# lamps_antenna.net
KiCad netlist of a schematic drawn in Altium Designer
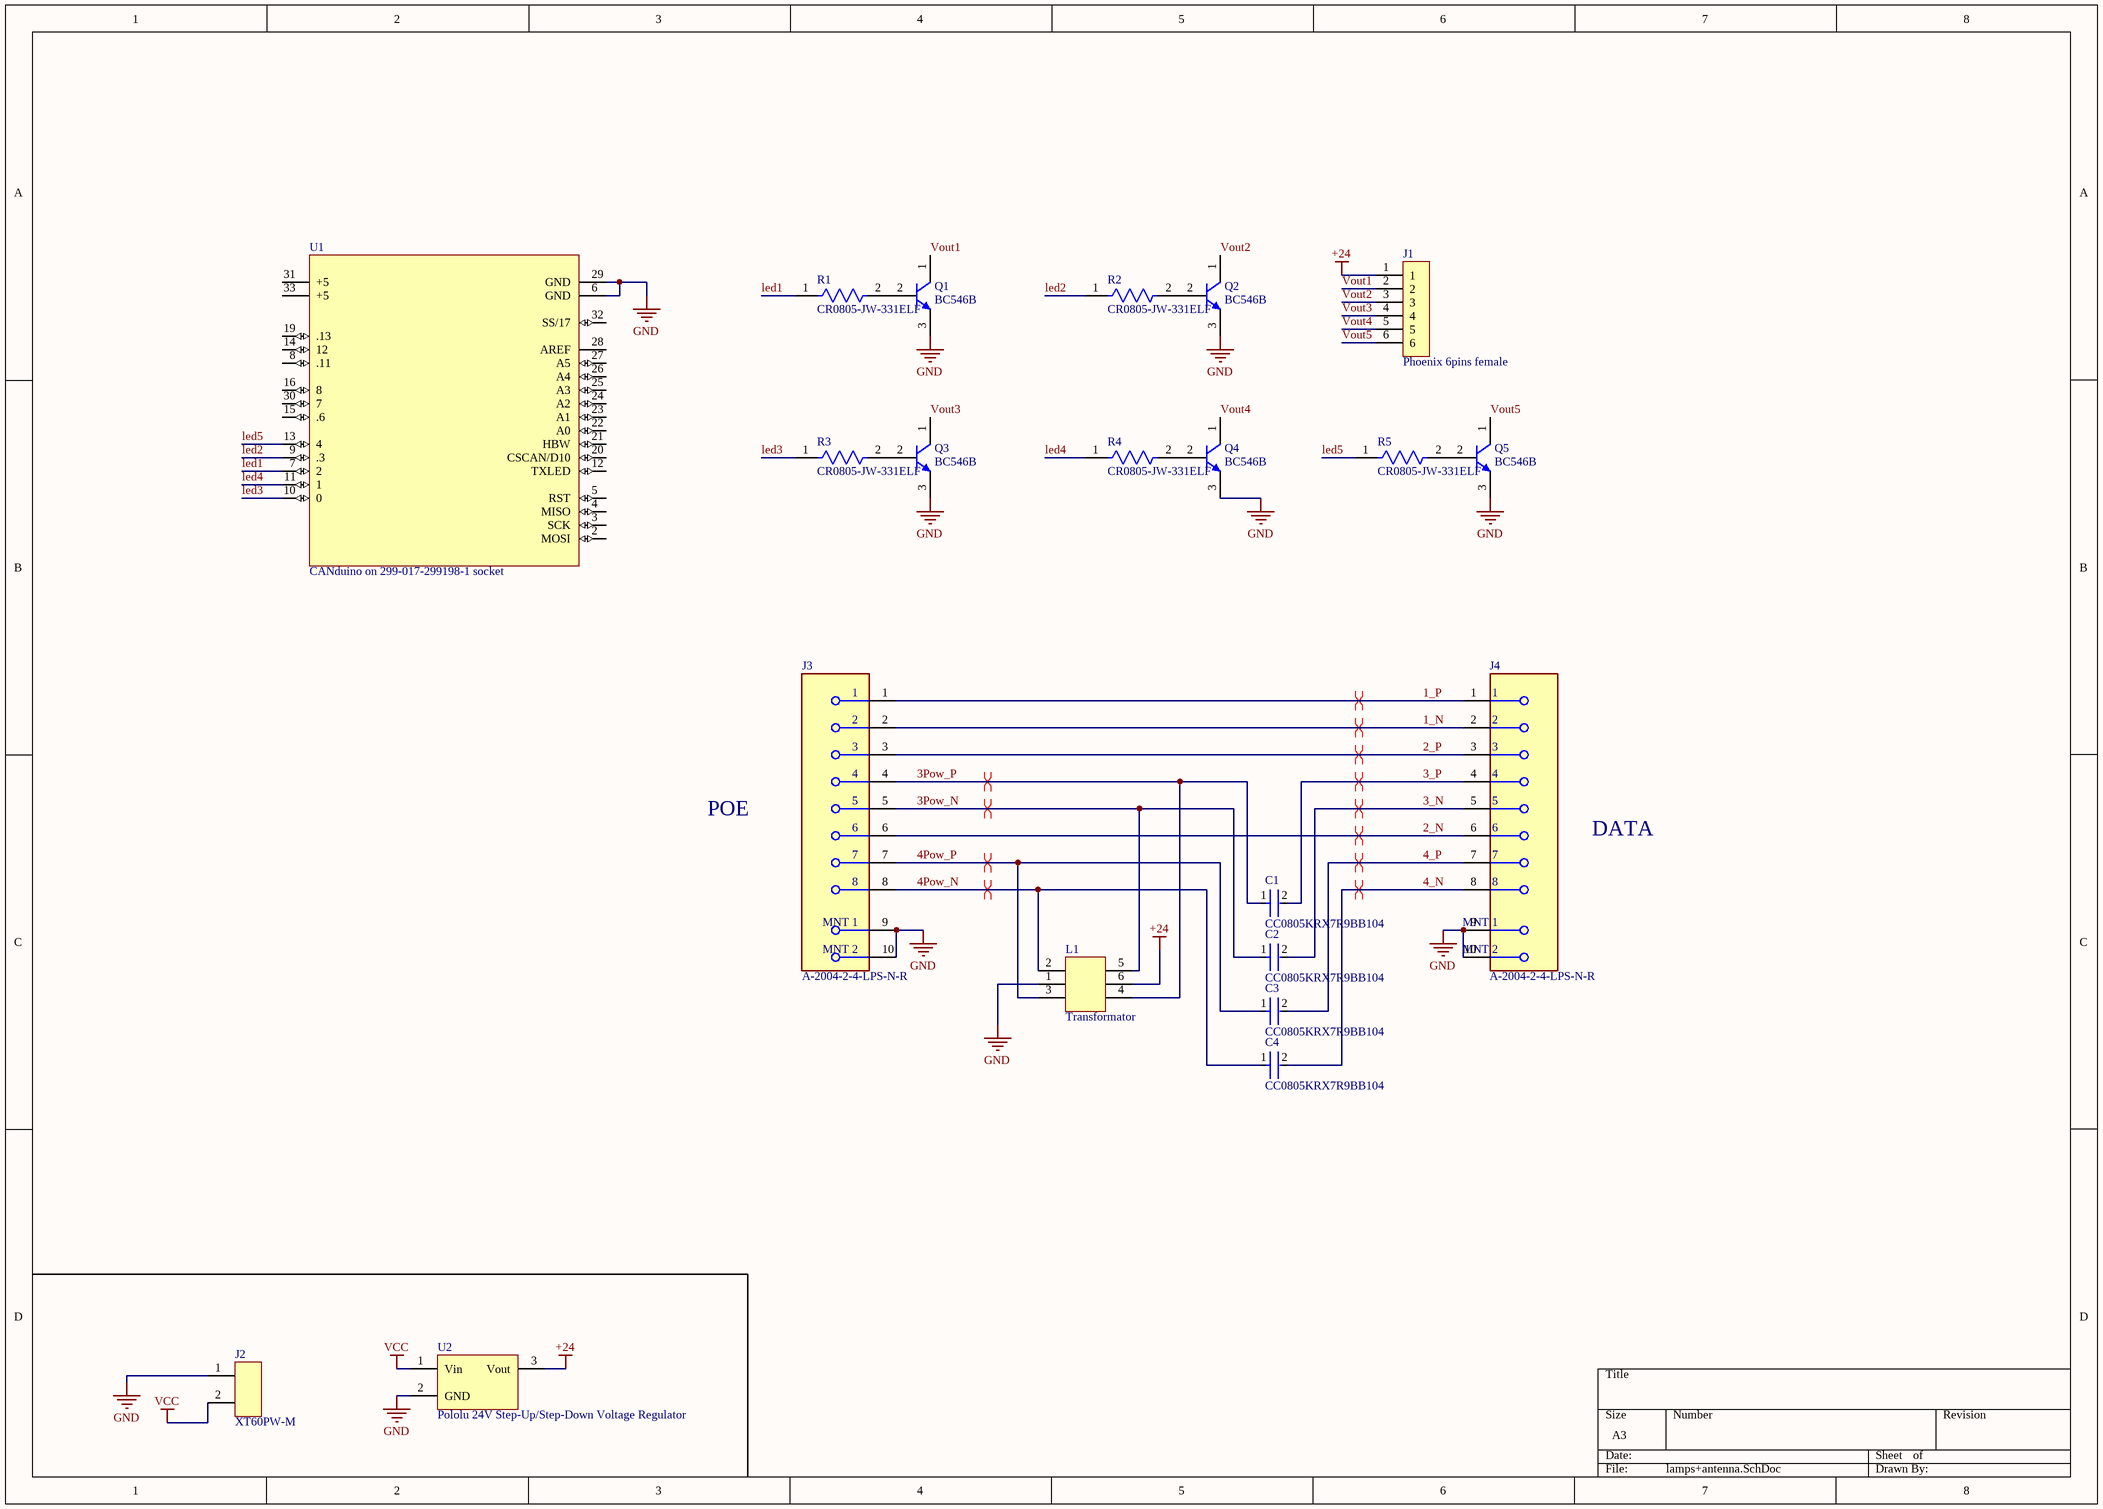
[diagram p0: lamps+antenna.SchDoc]

(export (version "E")
  (design (tool "Eeschema 10.0.6"))
  (components
    (comp (ref "C1")
      (value "CC0805KRX7R9BB104")
      (footprint "FP-CC0805-0_85-IPC_A")
      (description "CAP CER 0.1UF 50V X7R 0805")
      (fields (field (name "TOLERANCE") "0.1") (field (name "MANUFACTURER") "Yageo"))
      (libsource (lib "Altium Content Vault") (part "11868f565c42a9108669ba33697ecf6"))
    )
    (comp (ref "C2")
      (value "CC0805KRX7R9BB104")
      (footprint "FP-CC0805-0_85-IPC_A")
      (description "CAP CER 0.1UF 50V X7R 0805")
      (fields (field (name "TOLERANCE") "0.1") (field (name "MANUFACTURER") "Yageo"))
      (libsource (lib "Altium Content Vault") (part "11868f565c42a9108669ba33697ecf6"))
    )
    (comp (ref "C3")
      (value "CC0805KRX7R9BB104")
      (footprint "FP-CC0805-0_85-IPC_A")
      (description "CAP CER 0.1UF 50V X7R 0805")
      (fields (field (name "TOLERANCE") "0.1") (field (name "MANUFACTURER") "Yageo"))
      (libsource (lib "Altium Content Vault") (part "11868f565c42a9108669ba33697ecf6"))
    )
    (comp (ref "C4")
      (value "CC0805KRX7R9BB104")
      (footprint "FP-CC0805-0_85-IPC_A")
      (description "CAP CER 0.1UF 50V X7R 0805")
      (fields (field (name "TOLERANCE") "0.1") (field (name "MANUFACTURER") "Yageo"))
      (libsource (lib "Altium Content Vault") (part "11868f565c42a9108669ba33697ecf6"))
    )
    (comp (ref "J1")
      (value "Phoenix 6pins female")
      (footprint "Phoenix 6pins female")
      (libsource (lib "Lamps+antenna") (part "Phoenix 6pins female"))
    )
    (comp (ref "J2")
      (value "XT60PW-M")
      (footprint "XT60PW-M")
      (libsource (lib "Lamps+antenna") (part "XT60PW-M"))
    )
    (comp (ref "J3")
      (value "A-2004-2-4-LPS-N-R")
      (footprint "FP-A-2004-2-4-LPS-N-R-MFG")
      (description "CONN MOD JACK 8P8C R/A SHIELDED")
      (libsource (lib "Altium Content Vault") (part "834c2869e874bdac0884cd52cd10454"))
    )
    (comp (ref "J4")
      (value "A-2004-2-4-LPS-N-R")
      (footprint "FP-A-2004-2-4-LPS-N-R-MFG")
      (description "CONN MOD JACK 8P8C R/A SHIELDED")
      (libsource (lib "") (part "834c2869e874bdac0884cd52cd10454_1"))
    )
    (comp (ref "L1")
      (value "Transformator")
      (footprint "Transformator")
      (libsource (lib "Lamps+antenna") (part "Transformator"))
    )
    (comp (ref "Q1")
      (value "BC546B")
      (footprint "ONSC-TO-92-3-29-11")
      (description "Amplifier Transistor, NPN Silicon, 3-Pin TO-92, Bulk Box")
      (fields (field (name "MANUFACTURER") "On Semiconductor"))
      (libsource (lib "Altium Content Vault") (part "ONSC-NPN-C1B2E3-3"))
    )
    (comp (ref "Q2")
      (value "BC546B")
      (footprint "ONSC-TO-92-3-29-11")
      (description "Amplifier Transistor, NPN Silicon, 3-Pin TO-92, Bulk Box")
      (fields (field (name "MANUFACTURER") "On Semiconductor"))
      (libsource (lib "Altium Content Vault") (part "ONSC-NPN-C1B2E3-3"))
    )
    (comp (ref "Q3")
      (value "BC546B")
      (footprint "ONSC-TO-92-3-29-11")
      (description "Amplifier Transistor, NPN Silicon, 3-Pin TO-92, Bulk Box")
      (fields (field (name "MANUFACTURER") "On Semiconductor"))
      (libsource (lib "Altium Content Vault") (part "ONSC-NPN-C1B2E3-3"))
    )
    (comp (ref "Q4")
      (value "BC546B")
      (footprint "ONSC-TO-92-3-29-11")
      (description "Amplifier Transistor, NPN Silicon, 3-Pin TO-92, Bulk Box")
      (fields (field (name "MANUFACTURER") "On Semiconductor"))
      (libsource (lib "Altium Content Vault") (part "ONSC-NPN-C1B2E3-3"))
    )
    (comp (ref "Q5")
      (value "BC546B")
      (footprint "ONSC-TO-92-3-29-11")
      (description "Amplifier Transistor, NPN Silicon, 3-Pin TO-92, Bulk Box")
      (fields (field (name "MANUFACTURER") "On Semiconductor"))
      (libsource (lib "Altium Content Vault") (part "ONSC-NPN-C1B2E3-3"))
    )
    (comp (ref "R1")
      (value "CR0805-JW-331ELF")
      (footprint "FP-CR0805-MFG")
      (description "Thick Film Chip Resistors 0805 330Ω 0.125W 5% 200ppm/°C")
      (fields (field (name "TOLERANCE") "5%"))
      (libsource (lib "Altium Content Vault") (part "1029c3af85768c4190bb7ad29bc67b5"))
    )
    (comp (ref "R2")
      (value "CR0805-JW-331ELF")
      (footprint "FP-CR0805-MFG")
      (description "Thick Film Chip Resistors 0805 330Ω 0.125W 5% 200ppm/°C")
      (fields (field (name "TOLERANCE") "5%"))
      (libsource (lib "Altium Content Vault") (part "1029c3af85768c4190bb7ad29bc67b5"))
    )
    (comp (ref "R3")
      (value "CR0805-JW-331ELF")
      (footprint "FP-CR0805-MFG")
      (description "Thick Film Chip Resistors 0805 330Ω 0.125W 5% 200ppm/°C")
      (fields (field (name "TOLERANCE") "5%"))
      (libsource (lib "Altium Content Vault") (part "1029c3af85768c4190bb7ad29bc67b5"))
    )
    (comp (ref "R4")
      (value "CR0805-JW-331ELF")
      (footprint "FP-CR0805-MFG")
      (description "Thick Film Chip Resistors 0805 330Ω 0.125W 5% 200ppm/°C")
      (fields (field (name "TOLERANCE") "5%"))
      (libsource (lib "Altium Content Vault") (part "1029c3af85768c4190bb7ad29bc67b5"))
    )
    (comp (ref "R5")
      (value "CR0805-JW-331ELF")
      (footprint "FP-CR0805-MFG")
      (description "Thick Film Chip Resistors 0805 330Ω 0.125W 5% 200ppm/°C")
      (fields (field (name "TOLERANCE") "5%"))
      (libsource (lib "Altium Content Vault") (part "1029c3af85768c4190bb7ad29bc67b5"))
    )
    (comp (ref "U1")
      (value "CANduino on 299-017-299198-1 socket")
      (footprint "CANduino on 299-017-299198-1 socket")
      (description "CANduino board without pins 1, 17, 18 and 34 due to socket specification")
      (libsource (lib "CANduino") (part "CANduino on 299-017-299198-1 socket"))
    )
    (comp (ref "U2")
      (value "Pololu 24V Step-Up/Step-Down Voltage Regulator")
      (footprint "S18V20F12")
      (libsource (lib "Lamps+antenna") (part "S18V20F24"))
    )
  )
  (nets
    (net (code "1") (name "+24") (class "Default")
      (node (ref "J1") (pin "1") (pinfunction "1_1") (pintype "passive"))
      (node (ref "L1") (pin "6") (pintype "passive"))
      (node (ref "U2") (pin "3") (pinfunction "Vout_3") (pintype "passive"))
    )
    (net (code "2") (name "/1_N") (class "Default")
      (node (ref "J3") (pin "2") (pinfunction "2_2") (pintype "passive"))
      (node (ref "J4") (pin "2") (pinfunction "2_2") (pintype "passive"))
    )
    (net (code "3") (name "/1_P") (class "Default")
      (node (ref "J3") (pin "1") (pinfunction "1_1") (pintype "passive"))
      (node (ref "J4") (pin "1") (pinfunction "1_1") (pintype "passive"))
    )
    (net (code "4") (name "/2_N") (class "Default")
      (node (ref "J3") (pin "6") (pinfunction "6_6") (pintype "passive"))
      (node (ref "J4") (pin "6") (pinfunction "6_6") (pintype "passive"))
    )
    (net (code "5") (name "/2_P") (class "Default")
      (node (ref "J3") (pin "3") (pinfunction "3_3") (pintype "passive"))
      (node (ref "J4") (pin "3") (pinfunction "3_3") (pintype "passive"))
    )
    (net (code "6") (name "/3Pow_N") (class "Default")
      (node (ref "C2") (pin "1") (pinfunction "1_1") (pintype "passive"))
      (node (ref "J3") (pin "5") (pinfunction "5_5") (pintype "passive"))
      (node (ref "L1") (pin "5") (pintype "passive"))
    )
    (net (code "7") (name "/3Pow_P") (class "Default")
      (node (ref "C1") (pin "1") (pinfunction "1_1") (pintype "passive"))
      (node (ref "J3") (pin "4") (pinfunction "4_4") (pintype "passive"))
      (node (ref "L1") (pin "4") (pintype "passive"))
    )
    (net (code "8") (name "/3_N") (class "Default")
      (node (ref "C2") (pin "2") (pinfunction "2_2") (pintype "passive"))
      (node (ref "J4") (pin "5") (pinfunction "5_5") (pintype "passive"))
    )
    (net (code "9") (name "/3_P") (class "Default")
      (node (ref "C1") (pin "2") (pinfunction "2_2") (pintype "passive"))
      (node (ref "J4") (pin "4") (pinfunction "4_4") (pintype "passive"))
    )
    (net (code "10") (name "/4Pow_N") (class "Default")
      (node (ref "C4") (pin "1") (pinfunction "1_1") (pintype "passive"))
      (node (ref "J3") (pin "8") (pinfunction "8_8") (pintype "passive"))
      (node (ref "L1") (pin "2") (pintype "passive"))
    )
    (net (code "11") (name "/4Pow_P") (class "Default")
      (node (ref "C3") (pin "1") (pinfunction "1_1") (pintype "passive"))
      (node (ref "J3") (pin "7") (pinfunction "7_7") (pintype "passive"))
      (node (ref "L1") (pin "3") (pintype "passive"))
    )
    (net (code "12") (name "/4_N") (class "Default")
      (node (ref "C4") (pin "2") (pinfunction "2_2") (pintype "passive"))
      (node (ref "J4") (pin "8") (pinfunction "8_8") (pintype "passive"))
    )
    (net (code "13") (name "/4_P") (class "Default")
      (node (ref "C3") (pin "2") (pinfunction "2_2") (pintype "passive"))
      (node (ref "J4") (pin "7") (pinfunction "7_7") (pintype "passive"))
    )
    (net (code "14") (name "/Vout1") (class "Default")
      (node (ref "J1") (pin "2") (pinfunction "2_2") (pintype "passive"))
      (node (ref "Q1") (pin "1") (pinfunction "C_1") (pintype "passive"))
    )
    (net (code "15") (name "/Vout2") (class "Default")
      (node (ref "J1") (pin "3") (pinfunction "3_3") (pintype "passive"))
      (node (ref "Q2") (pin "1") (pinfunction "C_1") (pintype "passive"))
    )
    (net (code "16") (name "/Vout3") (class "Default")
      (node (ref "J1") (pin "4") (pinfunction "4_4") (pintype "passive"))
      (node (ref "Q3") (pin "1") (pinfunction "C_1") (pintype "passive"))
    )
    (net (code "17") (name "/Vout4") (class "Default")
      (node (ref "J1") (pin "5") (pinfunction "5_5") (pintype "passive"))
      (node (ref "Q4") (pin "1") (pinfunction "C_1") (pintype "passive"))
    )
    (net (code "18") (name "/Vout5") (class "Default")
      (node (ref "J1") (pin "6") (pinfunction "6_6") (pintype "passive"))
      (node (ref "Q5") (pin "1") (pinfunction "C_1") (pintype "passive"))
    )
    (net (code "19") (name "/led1") (class "Default")
      (node (ref "R1") (pin "1") (pinfunction "1_1") (pintype "passive"))
      (node (ref "U1") (pin "7") (pinfunction "2_7") (pintype "bidirectional"))
    )
    (net (code "20") (name "/led2") (class "Default")
      (node (ref "R2") (pin "1") (pinfunction "1_1") (pintype "passive"))
      (node (ref "U1") (pin "9") (pinfunction ".3_9") (pintype "bidirectional"))
    )
    (net (code "21") (name "/led3") (class "Default")
      (node (ref "R3") (pin "1") (pinfunction "1_1") (pintype "passive"))
      (node (ref "U1") (pin "10") (pinfunction "0_10") (pintype "bidirectional"))
    )
    (net (code "22") (name "/led4") (class "Default")
      (node (ref "R4") (pin "1") (pinfunction "1_1") (pintype "passive"))
      (node (ref "U1") (pin "11") (pinfunction "1_11") (pintype "bidirectional"))
    )
    (net (code "23") (name "/led5") (class "Default")
      (node (ref "R5") (pin "1") (pinfunction "1_1") (pintype "passive"))
      (node (ref "U1") (pin "13") (pinfunction "4_13") (pintype "bidirectional"))
    )
    (net (code "24") (name "GND") (class "Default")
      (node (ref "J2") (pin "1") (pintype "passive"))
      (node (ref "J3") (pin "10") (pinfunction "MNT_2_10") (pintype "passive"))
      (node (ref "J3") (pin "9") (pinfunction "MNT_1_9") (pintype "passive"))
      (node (ref "J4") (pin "10") (pinfunction "MNT_2_10") (pintype "passive"))
      (node (ref "J4") (pin "9") (pinfunction "MNT_1_9") (pintype "passive"))
      (node (ref "L1") (pin "1") (pintype "passive"))
      (node (ref "Q1") (pin "3") (pinfunction "E_3") (pintype "passive"))
      (node (ref "Q2") (pin "3") (pinfunction "E_3") (pintype "passive"))
      (node (ref "Q3") (pin "3") (pinfunction "E_3") (pintype "passive"))
      (node (ref "Q4") (pin "3") (pinfunction "E_3") (pintype "passive"))
      (node (ref "Q5") (pin "3") (pinfunction "E_3") (pintype "passive"))
      (node (ref "U1") (pin "29") (pinfunction "GND_29") (pintype "passive"))
      (node (ref "U1") (pin "6") (pinfunction "GND_6") (pintype "passive"))
      (node (ref "U2") (pin "2") (pinfunction "GND_2") (pintype "passive"))
    )
    (net (code "25") (name "Net-(Q1-B)") (class "Default")
      (node (ref "Q1") (pin "2") (pinfunction "B_2") (pintype "passive"))
      (node (ref "R1") (pin "2") (pinfunction "2_2") (pintype "passive"))
    )
    (net (code "26") (name "Net-(Q2-B)") (class "Default")
      (node (ref "Q2") (pin "2") (pinfunction "B_2") (pintype "passive"))
      (node (ref "R2") (pin "2") (pinfunction "2_2") (pintype "passive"))
    )
    (net (code "27") (name "Net-(Q3-B)") (class "Default")
      (node (ref "Q3") (pin "2") (pinfunction "B_2") (pintype "passive"))
      (node (ref "R3") (pin "2") (pinfunction "2_2") (pintype "passive"))
    )
    (net (code "28") (name "Net-(Q4-B)") (class "Default")
      (node (ref "Q4") (pin "2") (pinfunction "B_2") (pintype "passive"))
      (node (ref "R4") (pin "2") (pinfunction "2_2") (pintype "passive"))
    )
    (net (code "29") (name "Net-(Q5-B)") (class "Default")
      (node (ref "Q5") (pin "2") (pinfunction "B_2") (pintype "passive"))
      (node (ref "R5") (pin "2") (pinfunction "2_2") (pintype "passive"))
    )
    (net (code "30") (name "VCC") (class "Default")
      (node (ref "J2") (pin "2") (pintype "passive"))
      (node (ref "U2") (pin "1") (pinfunction "Vin_1") (pintype "passive"))
    )
    (net (code "31") (name "unconnected-(U1-+5-Pad31)") (class "Default")
      (node (ref "U1") (pin "31") (pinfunction "+5_31") (pintype "power_in"))
    )
    (net (code "32") (name "unconnected-(U1-+5-Pad33)") (class "Default")
      (node (ref "U1") (pin "33") (pinfunction "+5_33") (pintype "power_in"))
    )
    (net (code "33") (name "unconnected-(U1-.6-Pad15)") (class "Default")
      (node (ref "U1") (pin "15") (pinfunction ".6_15") (pintype "bidirectional"))
    )
    (net (code "34") (name "unconnected-(U1-.11-Pad8)") (class "Default")
      (node (ref "U1") (pin "8") (pinfunction ".11_8") (pintype "bidirectional"))
    )
    (net (code "35") (name "unconnected-(U1-.13-Pad19)") (class "Default")
      (node (ref "U1") (pin "19") (pinfunction ".13_19") (pintype "bidirectional"))
    )
    (net (code "36") (name "unconnected-(U1-7-Pad30)") (class "Default")
      (node (ref "U1") (pin "30") (pinfunction "7_30") (pintype "bidirectional"))
    )
    (net (code "37") (name "unconnected-(U1-8-Pad16)") (class "Default")
      (node (ref "U1") (pin "16") (pinfunction "8_16") (pintype "bidirectional"))
    )
    (net (code "38") (name "unconnected-(U1-12-Pad14)") (class "Default")
      (node (ref "U1") (pin "14") (pinfunction "12_14") (pintype "bidirectional"))
    )
    (net (code "39") (name "unconnected-(U1-A0-Pad22)") (class "Default")
      (node (ref "U1") (pin "22") (pinfunction "A0_22") (pintype "bidirectional"))
    )
    (net (code "40") (name "unconnected-(U1-A1-Pad23)") (class "Default")
      (node (ref "U1") (pin "23") (pinfunction "A1_23") (pintype "bidirectional"))
    )
    (net (code "41") (name "unconnected-(U1-A2-Pad24)") (class "Default")
      (node (ref "U1") (pin "24") (pinfunction "A2_24") (pintype "bidirectional"))
    )
    (net (code "42") (name "unconnected-(U1-A3-Pad25)") (class "Default")
      (node (ref "U1") (pin "25") (pinfunction "A3_25") (pintype "bidirectional"))
    )
    (net (code "43") (name "unconnected-(U1-A4-Pad26)") (class "Default")
      (node (ref "U1") (pin "26") (pinfunction "A4_26") (pintype "bidirectional"))
    )
    (net (code "44") (name "unconnected-(U1-A5-Pad27)") (class "Default")
      (node (ref "U1") (pin "27") (pinfunction "A5_27") (pintype "bidirectional"))
    )
    (net (code "45") (name "unconnected-(U1-AREF-Pad28)") (class "Default")
      (node (ref "U1") (pin "28") (pinfunction "AREF_28") (pintype "passive"))
    )
    (net (code "46") (name "unconnected-(U1-CSCAN{slash}D10-Pad20)") (class "Default")
      (node (ref "U1") (pin "20") (pinfunction "CSCAN/D10_20") (pintype "bidirectional"))
    )
    (net (code "47") (name "unconnected-(U1-HBW-Pad21)") (class "Default")
      (node (ref "U1") (pin "21") (pinfunction "HBW_21") (pintype "bidirectional"))
    )
    (net (code "48") (name "unconnected-(U1-MISO-Pad4)") (class "Default")
      (node (ref "U1") (pin "4") (pinfunction "MISO_4") (pintype "bidirectional"))
    )
    (net (code "49") (name "unconnected-(U1-MOSI-Pad2)") (class "Default")
      (node (ref "U1") (pin "2") (pinfunction "MOSI_2") (pintype "bidirectional"))
    )
    (net (code "50") (name "unconnected-(U1-RST-Pad5)") (class "Default")
      (node (ref "U1") (pin "5") (pinfunction "RST_5") (pintype "bidirectional"))
    )
    (net (code "51") (name "unconnected-(U1-SCK-Pad3)") (class "Default")
      (node (ref "U1") (pin "3") (pinfunction "SCK_3") (pintype "bidirectional"))
    )
    (net (code "52") (name "unconnected-(U1-SS{slash}17-Pad32)") (class "Default")
      (node (ref "U1") (pin "32") (pinfunction "SS/17_32") (pintype "bidirectional"))
    )
    (net (code "53") (name "unconnected-(U1-TXLED-Pad12)") (class "Default")
      (node (ref "U1") (pin "12") (pinfunction "TXLED_12") (pintype "bidirectional"))
    )
  )
)
